# TP_IHM_7SEG.net
KiCad netlist of a schematic drawn in Altium Designer
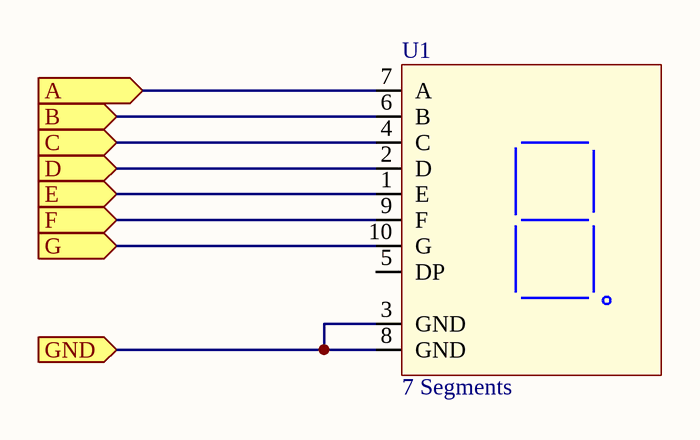
[diagram p0: TP_IHM_7SEG.SchDoc]

(export (version "E")
  (design (tool "Eeschema 10.0.6"))
  (components
    (comp (ref "U1")
      (value "7 Segments")
      (footprint "SA10-21GWA")
      (description "KingBright Led 7 Segments")
      (libsource (lib "TpGiven") (part "SC10-21SRWA"))
    )
  )
  (nets
    (net (code "1") (name "/A") (class "Default")
      (node (ref "U1") (pin "7") (pinfunction "A_7") (pintype "passive"))
    )
    (net (code "2") (name "/B") (class "Default")
      (node (ref "U1") (pin "6") (pinfunction "B_6") (pintype "passive"))
    )
    (net (code "3") (name "/C") (class "Default")
      (node (ref "U1") (pin "4") (pinfunction "C_4") (pintype "passive"))
    )
    (net (code "4") (name "/D") (class "Default")
      (node (ref "U1") (pin "2") (pinfunction "D_2") (pintype "passive"))
    )
    (net (code "5") (name "/E") (class "Default")
      (node (ref "U1") (pin "1") (pinfunction "E_1") (pintype "passive"))
    )
    (net (code "6") (name "/F") (class "Default")
      (node (ref "U1") (pin "9") (pinfunction "F_9") (pintype "passive"))
    )
    (net (code "7") (name "/G") (class "Default")
      (node (ref "U1") (pin "10") (pinfunction "G_10") (pintype "passive"))
    )
    (net (code "8") (name "/GND") (class "Default")
      (node (ref "U1") (pin "3") (pinfunction "GND_3") (pintype "passive"))
      (node (ref "U1") (pin "8") (pinfunction "GND_8") (pintype "passive"))
    )
    (net (code "9") (name "unconnected-(U1-DP-Pad5)") (class "Default")
      (node (ref "U1") (pin "5") (pinfunction "DP_5") (pintype "passive"))
    )
  )
)
